# 02_Power.net
KiCad netlist of a schematic drawn in Altium Designer
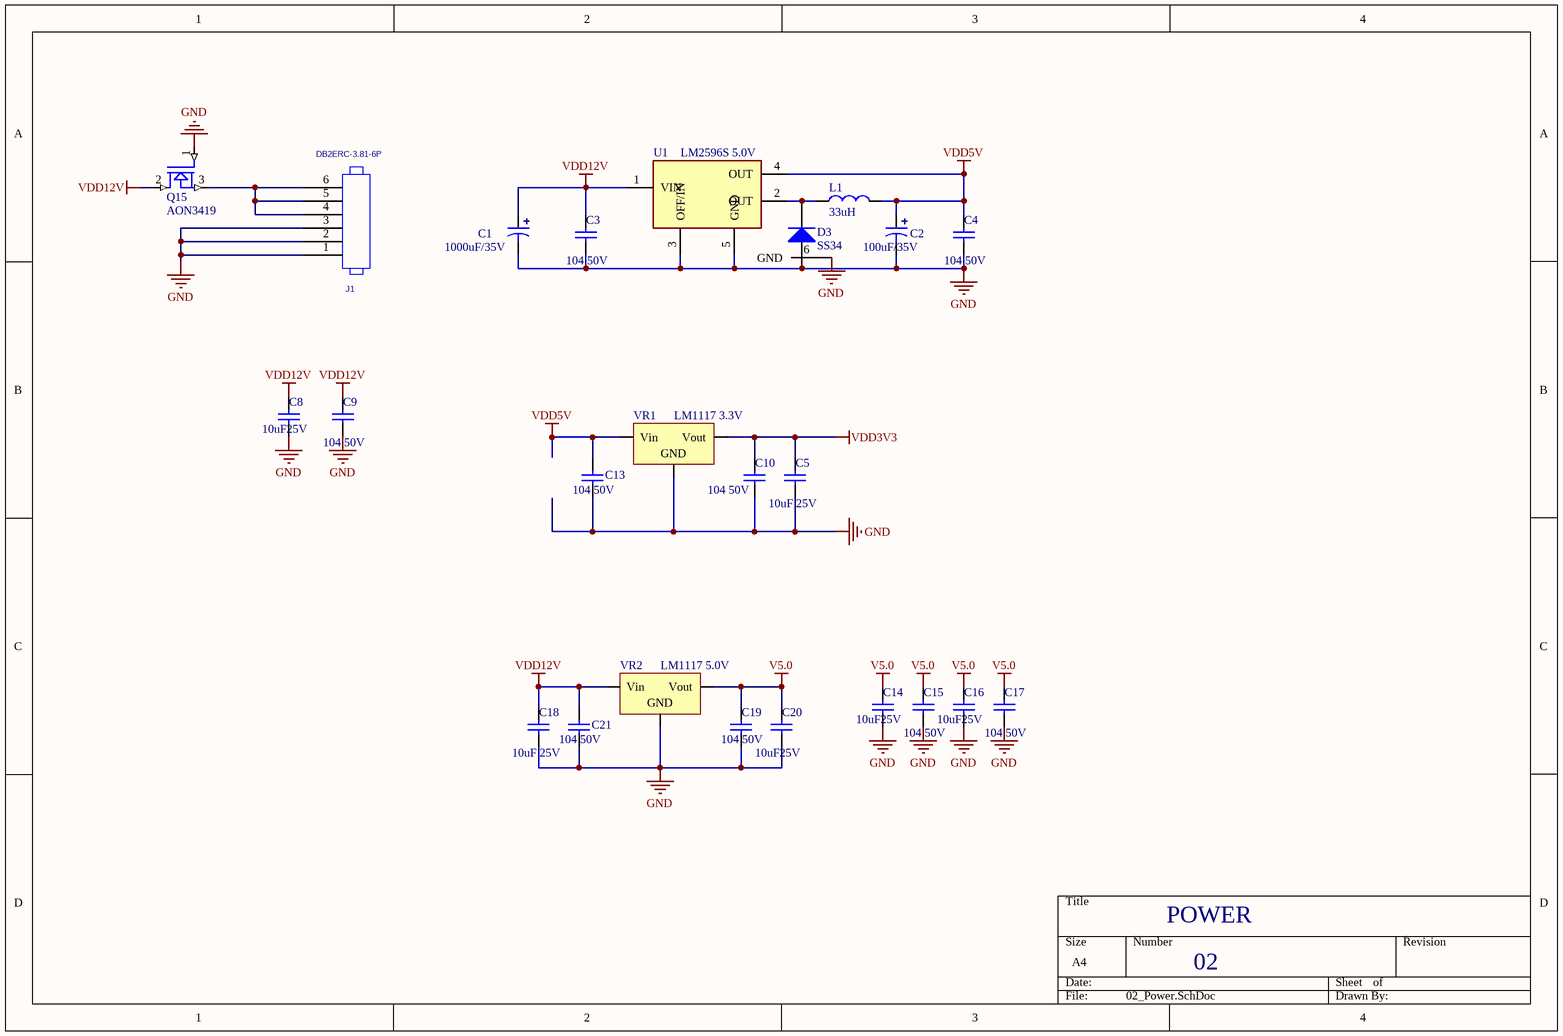
[diagram p0: 02_Power.SchDoc]

(export (version "E")
  (design (tool "Eeschema 10.0.6"))
  (components
    (comp (ref "C1")
      (value "1000uF/35V")
      (footprint "10*16")
      (description "电解电容")
      (libsource (lib "XiaoyI") (part "CAP2"))
    )
    (comp (ref "C2")
      (value "100uF/35V")
      (footprint "6*8")
      (description "电解电容")
      (libsource (lib "XiaoyI") (part "CAP2"))
    )
    (comp (ref "C3")
      (value "104 50V")
      (footprint "SMD-0805C")
      (description "贴片电容 10%")
      (libsource (lib "XiaoyI") (part "CAP4"))
    )
    (comp (ref "C4")
      (value "104 50V")
      (footprint "SMD-0805C")
      (description "贴片电容 10%")
      (libsource (lib "XiaoyI") (part "CAP4"))
    )
    (comp (ref "C5")
      (value "10uF 25V")
      (footprint "SMD-0603C")
      (description "贴片电容 20%")
      (libsource (lib "XiaoyI") (part "CAP4"))
    )
    (comp (ref "C8")
      (value "10uF25V")
      (footprint "SMD-0603C")
      (description "贴片电容 10%")
      (libsource (lib "XiaoyI") (part "CAP4"))
    )
    (comp (ref "C9")
      (value "104 50V")
      (footprint "SMD-0603C")
      (description "贴片电容 10%")
      (libsource (lib "XiaoyI") (part "CAP4"))
    )
    (comp (ref "C10")
      (value "104 50V")
      (footprint "SMD-0603C")
      (description "贴片电容 10%")
      (libsource (lib "XiaoyI") (part "CAP4"))
    )
    (comp (ref "C13")
      (value "104 50V")
      (footprint "SMD-0603C")
      (description "贴片电容 10%")
      (libsource (lib "XiaoyI") (part "CAP4"))
    )
    (comp (ref "C14")
      (value "10uF25V")
      (footprint "SMD-0603C")
      (description "贴片电容 20%")
      (libsource (lib "XiaoyI") (part "CAP4"))
    )
    (comp (ref "C15")
      (value "104 50V")
      (footprint "SMD-0603C")
      (description "贴片电容 20%")
      (libsource (lib "XiaoyI") (part "CAP4"))
    )
    (comp (ref "C16")
      (value "10uF25V")
      (footprint "SMD-0603C")
      (description "贴片电容 20%")
      (libsource (lib "XiaoyI") (part "CAP4"))
    )
    (comp (ref "C17")
      (value "104 50V")
      (footprint "SMD-0603C")
      (description "贴片电容 20%")
      (libsource (lib "XiaoyI") (part "CAP4"))
    )
    (comp (ref "C18")
      (value "10uF 25V")
      (footprint "SMD-0603C")
      (description "贴片电容 20%")
      (libsource (lib "XiaoyI") (part "CAP4"))
    )
    (comp (ref "C19")
      (value "104 50V")
      (footprint "SMD-0603C")
      (description "贴片电容 20%")
      (libsource (lib "XiaoyI") (part "CAP4"))
    )
    (comp (ref "C20")
      (value "10uF25V")
      (footprint "SMD-0603C")
      (description "贴片电容 20%")
      (libsource (lib "XiaoyI") (part "CAP4"))
    )
    (comp (ref "C21")
      (value "104 50V")
      (footprint "SMD-0603C")
      (description "贴片电容 20%")
      (libsource (lib "XiaoyI") (part "CAP4"))
    )
    (comp (ref "D3") (value "SS34") (footprint "SMA") (libsource (lib "Sch_library") (part "DIODE")))
    (comp (ref "J1")
      (value "DB2ERC-3.81-6P")
      (footprint "DB2ERC-3P81-6P")
      (fields (field (name "Comment") "HEADER_6"))
      (libsource (lib "liujingtao_V1.0") (part "HEADER_6"))
    )
    (comp (ref "L1") (value "33uH") (footprint "CDRH-127") (libsource (lib "Sch_library") (part "IND")))
    (comp (ref "Q15")
      (value "AON3419")
      (footprint "DFN3*3-8")
      (description "MOSFET N")
      (libsource (lib "XiaoyI") (part "MOSFET N"))
    )
    (comp (ref "U1")
      (value "LM2596S 5.0V")
      (footprint "TO-263-5")
      (libsource (lib "Sch_library") (part "LM2596"))
    )
    (comp (ref "VR1")
      (value "LM1117 3.3V")
      (footprint "SOT223")
      (description "三端稳压器")
      (libsource (lib "XiaoyI") (part "LM1117"))
    )
    (comp (ref "VR2")
      (value "LM1117 5.0V")
      (footprint "SOT223")
      (description "三端稳压器 （耐压20V）")
      (libsource (lib "XiaoyI") (part "LM1117"))
    )
  )
  (nets
    (net (code "1") (name "GND") (class "Default")
      (node (ref "C1") (pin "2") (pinfunction "2_2") (pintype "passive"))
      (node (ref "C10") (pin "1") (pinfunction "1_1") (pintype "passive"))
      (node (ref "C13") (pin "1") (pinfunction "1_1") (pintype "passive"))
      (node (ref "C14") (pin "1") (pinfunction "1_1") (pintype "passive"))
      (node (ref "C15") (pin "1") (pinfunction "1_1") (pintype "passive"))
      (node (ref "C16") (pin "1") (pinfunction "1_1") (pintype "passive"))
      (node (ref "C17") (pin "1") (pinfunction "1_1") (pintype "passive"))
      (node (ref "C18") (pin "1") (pinfunction "1_1") (pintype "passive"))
      (node (ref "C19") (pin "1") (pinfunction "1_1") (pintype "passive"))
      (node (ref "C2") (pin "2") (pinfunction "2_2") (pintype "passive"))
      (node (ref "C20") (pin "1") (pinfunction "1_1") (pintype "passive"))
      (node (ref "C21") (pin "1") (pinfunction "1_1") (pintype "passive"))
      (node (ref "C3") (pin "1") (pinfunction "1_1") (pintype "passive"))
      (node (ref "C4") (pin "1") (pinfunction "1_1") (pintype "passive"))
      (node (ref "C5") (pin "1") (pinfunction "1_1") (pintype "passive"))
      (node (ref "C8") (pin "1") (pinfunction "1_1") (pintype "passive"))
      (node (ref "C9") (pin "1") (pinfunction "1_1") (pintype "passive"))
      (node (ref "D3") (pin "1") (pinfunction "A_1") (pintype "passive"))
      (node (ref "J1") (pin "1") (pinfunction "1_1") (pintype "passive"))
      (node (ref "J1") (pin "2") (pinfunction "2_2") (pintype "passive"))
      (node (ref "J1") (pin "3") (pinfunction "3_3") (pintype "passive"))
      (node (ref "Q15") (pin "1") (pinfunction "G_1") (pintype "input"))
      (node (ref "U1") (pin "3") (pinfunction "OFF/IN_3") (pintype "passive"))
      (node (ref "U1") (pin "5") (pinfunction "GND_5") (pintype "passive"))
      (node (ref "U1") (pin "6") (pinfunction "GND_6") (pintype "passive"))
      (node (ref "VR1") (pin "1") (pinfunction "GND_1") (pintype "passive"))
      (node (ref "VR2") (pin "1") (pinfunction "GND_1") (pintype "passive"))
    )
    (net (code "2") (name "Net-(D3-K)") (class "Default")
      (node (ref "D3") (pin "2") (pinfunction "K_2") (pintype "passive"))
      (node (ref "L1") (pin "1") (pinfunction "1_1") (pintype "passive"))
      (node (ref "U1") (pin "2") (pinfunction "OUT_2") (pintype "passive"))
    )
    (net (code "3") (name "Net-(Q15-S)") (class "Default")
      (node (ref "J1") (pin "4") (pinfunction "4_4") (pintype "passive"))
      (node (ref "J1") (pin "5") (pinfunction "5_5") (pintype "passive"))
      (node (ref "J1") (pin "6") (pinfunction "6_6") (pintype "passive"))
      (node (ref "Q15") (pin "3") (pinfunction "S_3") (pintype "output"))
    )
    (net (code "4") (name "V5.0") (class "Default")
      (node (ref "C14") (pin "2") (pinfunction "2_2") (pintype "passive"))
      (node (ref "C15") (pin "2") (pinfunction "2_2") (pintype "passive"))
      (node (ref "C16") (pin "2") (pinfunction "2_2") (pintype "passive"))
      (node (ref "C17") (pin "2") (pinfunction "2_2") (pintype "passive"))
      (node (ref "C19") (pin "2") (pinfunction "2_2") (pintype "passive"))
      (node (ref "C20") (pin "2") (pinfunction "2_2") (pintype "passive"))
      (node (ref "VR2") (pin "2") (pinfunction "Vout_2") (pintype "passive"))
    )
    (net (code "5") (name "VDD3V3") (class "Default")
      (node (ref "C10") (pin "2") (pinfunction "2_2") (pintype "passive"))
      (node (ref "C5") (pin "2") (pinfunction "2_2") (pintype "passive"))
      (node (ref "VR1") (pin "2") (pinfunction "Vout_2") (pintype "passive"))
    )
    (net (code "6") (name "VDD5V") (class "Default")
      (node (ref "C13") (pin "2") (pinfunction "2_2") (pintype "passive"))
      (node (ref "C2") (pin "1") (pinfunction "1_1") (pintype "passive"))
      (node (ref "C4") (pin "2") (pinfunction "2_2") (pintype "passive"))
      (node (ref "L1") (pin "2") (pinfunction "2_2") (pintype "passive"))
      (node (ref "U1") (pin "4") (pinfunction "OUT_4") (pintype "passive"))
      (node (ref "VR1") (pin "3") (pinfunction "Vin_3") (pintype "passive"))
    )
    (net (code "7") (name "VDD12V") (class "Default")
      (node (ref "C1") (pin "1") (pinfunction "1_1") (pintype "passive"))
      (node (ref "C18") (pin "2") (pinfunction "2_2") (pintype "passive"))
      (node (ref "C21") (pin "2") (pinfunction "2_2") (pintype "passive"))
      (node (ref "C3") (pin "2") (pinfunction "2_2") (pintype "passive"))
      (node (ref "C8") (pin "2") (pinfunction "2_2") (pintype "passive"))
      (node (ref "C9") (pin "2") (pinfunction "2_2") (pintype "passive"))
      (node (ref "Q15") (pin "2") (pinfunction "D_2") (pintype "input"))
      (node (ref "U1") (pin "1") (pinfunction "VIN_1") (pintype "passive"))
      (node (ref "VR2") (pin "3") (pinfunction "Vin_3") (pintype "passive"))
    )
  )
)
